# Pixie.net
KiCad netlist of a schematic drawn in EAGLE
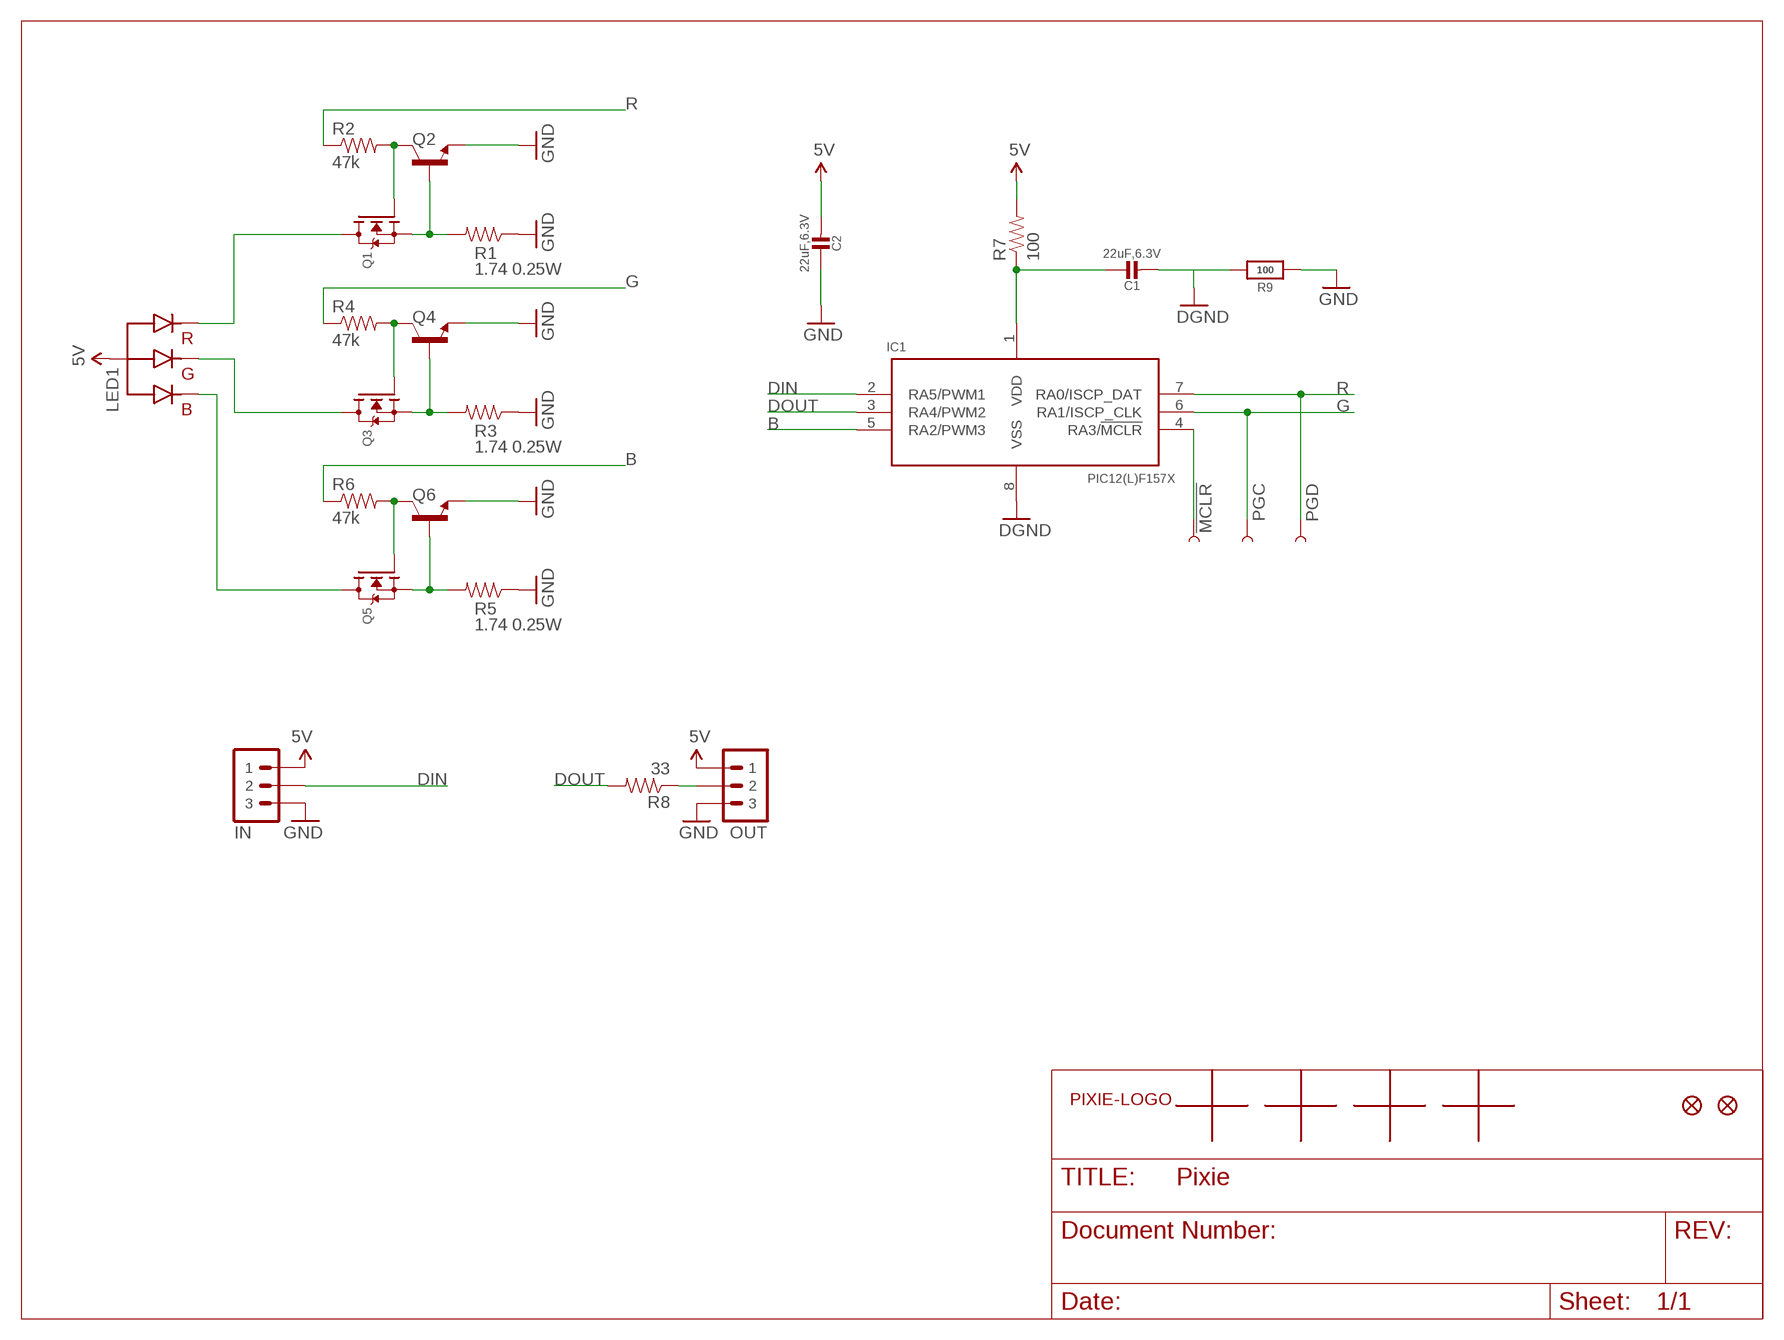
[diagram p0: schematic, sheet 1]

(export (version "E")
  (design (tool "Eeschema 10.0.6"))
  (components
    (comp (ref "!MCLR")
      (value "TEST-POINT3X4")
      (footprint "eagle-import:PAD.03X.04")
      (libsource (lib "eagle-import") (part "TEST-POINT3X4"))
    )
    (comp (ref "C1")
      (value "22uF,6.3V")
      (footprint "eagle-import:_0805MP")
      (libsource (lib "eagle-import") (part "CAP_CERAMIC_0805MP"))
    )
    (comp (ref "C2")
      (value "22uF,6.3V")
      (footprint "eagle-import:_0805MP")
      (libsource (lib "eagle-import") (part "CAP_CERAMIC_0805MP"))
    )
    (comp (ref "IC1")
      (value "PIC12(L)F157X")
      (footprint "eagle-import:MSOP-8")
      (libsource (lib "eagle-import") (part "PIC12(L)F157X"))
    )
    (comp (ref "IN")
      (value "M030.1PWR+SIG")
      (footprint "eagle-import:1X03-0.1PWR+SIG")
      (libsource (lib "eagle-import") (part "M030.1PWR+SIG"))
    )
    (comp (ref "LED1")
      (value "RGBLED_CA")
      (footprint "eagle-import:RGBLED3W4PIN")
      (libsource (lib "eagle-import") (part "RGBLED_CA"))
    )
    (comp (ref "OUT")
      (value "M030.1PWR+SIG")
      (footprint "eagle-import:1X03-0.1PWR+SIG")
      (libsource (lib "eagle-import") (part "M030.1PWR+SIG"))
    )
    (comp (ref "PGC")
      (value "TEST-POINT3X4")
      (footprint "eagle-import:PAD.03X.04")
      (libsource (lib "eagle-import") (part "TEST-POINT3X4"))
    )
    (comp (ref "PGD")
      (value "TEST-POINT3X4")
      (footprint "eagle-import:PAD.03X.04")
      (libsource (lib "eagle-import") (part "TEST-POINT3X4"))
    )
    (comp (ref "Q1")
      (value "IRLML2060TRPBF")
      (footprint "eagle-import:SOT23-3")
      (libsource (lib "eagle-import") (part "IRLML2060TRPBF"))
    )
    (comp (ref "Q2")
      (value "MMBT2222A")
      (footprint "eagle-import:SOT23-3")
      (libsource (lib "eagle-import") (part "MMBT2222A"))
    )
    (comp (ref "Q3")
      (value "IRLML2060TRPBF")
      (footprint "eagle-import:SOT23-3")
      (libsource (lib "eagle-import") (part "IRLML2060TRPBF"))
    )
    (comp (ref "Q4")
      (value "MMBT2222A")
      (footprint "eagle-import:SOT23-3")
      (libsource (lib "eagle-import") (part "MMBT2222A"))
    )
    (comp (ref "Q5")
      (value "IRLML2060TRPBF")
      (footprint "eagle-import:SOT23-3")
      (libsource (lib "eagle-import") (part "IRLML2060TRPBF"))
    )
    (comp (ref "Q6")
      (value "MMBT2222A")
      (footprint "eagle-import:SOT23-3")
      (libsource (lib "eagle-import") (part "MMBT2222A"))
    )
    (comp (ref "R1")
      (value "1.74 0.25W")
      (footprint "eagle-import:1206")
      (libsource (lib "eagle-import") (part "SparkFun-Resistors_RESISTOR1206"))
    )
    (comp (ref "R2")
      (value "47k")
      (footprint "eagle-import:0603-RES")
      (libsource (lib "eagle-import") (part "RESISTOR0603"))
    )
    (comp (ref "R3")
      (value "1.74 0.25W")
      (footprint "eagle-import:1206")
      (libsource (lib "eagle-import") (part "SparkFun-Resistors_RESISTOR1206"))
    )
    (comp (ref "R4")
      (value "47k")
      (footprint "eagle-import:0603-RES")
      (libsource (lib "eagle-import") (part "RESISTOR0603"))
    )
    (comp (ref "R5")
      (value "1.74 0.25W")
      (footprint "eagle-import:1206")
      (libsource (lib "eagle-import") (part "SparkFun-Resistors_RESISTOR1206"))
    )
    (comp (ref "R6")
      (value "47k")
      (footprint "eagle-import:0603-RES")
      (libsource (lib "eagle-import") (part "RESISTOR0603"))
    )
    (comp (ref "R7")
      (value "100")
      (footprint "eagle-import:0603-RES")
      (libsource (lib "eagle-import") (part "RESISTOR0603"))
    )
    (comp (ref "R8")
      (value "33")
      (footprint "eagle-import:0603-RES")
      (libsource (lib "eagle-import") (part "RESISTOR0603"))
    )
    (comp (ref "R9")
      (value "100")
      (footprint "eagle-import:_0603MP")
      (libsource (lib "eagle-import") (part "RESISTOR_0603MP"))
    )
    (comp (ref "U$1")
      (value "ALIGN_CROSS")
      (footprint "eagle-import:ALIGN_CROSS")
      (libsource (lib "eagle-import") (part "ALIGN_CROSS"))
    )
    (comp (ref "U$2")
      (value "ALIGN_CROSS")
      (footprint "eagle-import:ALIGN_CROSS")
      (libsource (lib "eagle-import") (part "ALIGN_CROSS"))
    )
    (comp (ref "U$3")
      (value "ALIGN_CROSS")
      (footprint "eagle-import:ALIGN_CROSS")
      (libsource (lib "eagle-import") (part "ALIGN_CROSS"))
    )
    (comp (ref "U$4")
      (value "ALIGN_CROSS")
      (footprint "eagle-import:ALIGN_CROSS")
      (libsource (lib "eagle-import") (part "ALIGN_CROSS"))
    )
    (comp (ref "U$5")
      (value "PIXIE-LOGO")
      (footprint "eagle-import:PIXIE-LOGO")
      (libsource (lib "eagle-import") (part "PIXIE-LOGO"))
    )
    (comp (ref "U$6")
      (value "FIDUCIAL\"\"")
      (footprint "eagle-import:FIDUCIAL_1MM")
      (libsource (lib "eagle-import") (part "FIDUCIAL{dblquote}{dblquote}"))
    )
    (comp (ref "U$7")
      (value "FIDUCIAL\"\"")
      (footprint "eagle-import:FIDUCIAL_1MM")
      (libsource (lib "eagle-import") (part "FIDUCIAL{dblquote}{dblquote}"))
    )
  )
  (nets
    (net (code "1") (name "/B") (class "Default")
      (node (ref "IC1") (pin "5") (pinfunction "RA2/PWM3_5") (pintype "bidirectional"))
      (node (ref "R6") (pin "1") (pinfunction "1_1") (pintype "passive"))
    )
    (net (code "2") (name "/DIN") (class "Default")
      (node (ref "IC1") (pin "2") (pinfunction "RA5/PWM1_2") (pintype "bidirectional"))
      (node (ref "IN") (pin "P$2") (pinfunction "2_P$2") (pintype "passive"))
    )
    (net (code "3") (name "/DOUT") (class "Default")
      (node (ref "IC1") (pin "3") (pinfunction "RA4/PWM2_3") (pintype "bidirectional"))
      (node (ref "R8") (pin "2") (pinfunction "2_2") (pintype "passive"))
    )
    (net (code "4") (name "/G") (class "Default")
      (node (ref "IC1") (pin "6") (pinfunction "RA1/ISCP_CLK_6") (pintype "bidirectional"))
      (node (ref "PGC") (pin "P$1") (pinfunction "1_P$1") (pintype "bidirectional"))
      (node (ref "R4") (pin "1") (pinfunction "1_1") (pintype "passive"))
    )
    (net (code "5") (name "/R") (class "Default")
      (node (ref "IC1") (pin "7") (pinfunction "RA0/ISCP_DAT_7") (pintype "bidirectional"))
      (node (ref "PGD") (pin "P$1") (pinfunction "1_P$1") (pintype "bidirectional"))
      (node (ref "R2") (pin "1") (pinfunction "1_1") (pintype "passive"))
    )
    (net (code "6") (name "5V") (class "Default")
      (node (ref "C2") (pin "2") (pinfunction "2_2") (pintype "passive"))
      (node (ref "IN") (pin "P$1") (pinfunction "1_P$1") (pintype "passive"))
      (node (ref "LED1") (pin "ANODE") (pinfunction "VCC_ANODE") (pintype "bidirectional"))
      (node (ref "OUT") (pin "P$1") (pinfunction "1_P$1") (pintype "passive"))
      (node (ref "R7") (pin "2") (pinfunction "2_2") (pintype "passive"))
    )
    (net (code "7") (name "DGND") (class "Default")
      (node (ref "C1") (pin "2") (pinfunction "2_2") (pintype "passive"))
      (node (ref "IC1") (pin "8") (pinfunction "VSS_8") (pintype "power_in"))
      (node (ref "R9") (pin "2") (pinfunction "2_2") (pintype "passive"))
    )
    (net (code "8") (name "GND") (class "Default")
      (node (ref "C2") (pin "1") (pinfunction "1_1") (pintype "passive"))
      (node (ref "IN") (pin "P$3") (pinfunction "3_P$3") (pintype "passive"))
      (node (ref "OUT") (pin "P$3") (pinfunction "3_P$3") (pintype "passive"))
      (node (ref "Q2") (pin "2") (pinfunction "E_2") (pintype "passive"))
      (node (ref "Q4") (pin "2") (pinfunction "E_2") (pintype "passive"))
      (node (ref "Q6") (pin "2") (pinfunction "E_2") (pintype "passive"))
      (node (ref "R1") (pin "1") (pinfunction "1_1") (pintype "passive"))
      (node (ref "R3") (pin "1") (pinfunction "1_1") (pintype "passive"))
      (node (ref "R5") (pin "1") (pinfunction "1_1") (pintype "passive"))
      (node (ref "R9") (pin "1") (pinfunction "1_1") (pintype "passive"))
    )
    (net (code "9") (name "Net-(!MCLR-1)") (class "Default")
      (node (ref "!MCLR") (pin "P$1") (pinfunction "1_P$1") (pintype "bidirectional"))
      (node (ref "IC1") (pin "4") (pinfunction "RA3/~{MCLR}_4") (pintype "bidirectional"))
    )
    (net (code "10") (name "Net-(IC1-VDD)") (class "Default")
      (node (ref "C1") (pin "1") (pinfunction "1_1") (pintype "passive"))
      (node (ref "IC1") (pin "1") (pinfunction "VDD_1") (pintype "power_in"))
      (node (ref "R7") (pin "1") (pinfunction "1_1") (pintype "passive"))
    )
    (net (code "11") (name "Net-(LED1-BLUE)") (class "Default")
      (node (ref "LED1") (pin "B") (pinfunction "BLUE_B") (pintype "bidirectional"))
      (node (ref "Q5") (pin "3") (pinfunction "D_3") (pintype "bidirectional"))
    )
    (net (code "12") (name "Net-(LED1-GREEN)") (class "Default")
      (node (ref "LED1") (pin "G") (pinfunction "GREEN_G") (pintype "bidirectional"))
      (node (ref "Q3") (pin "3") (pinfunction "D_3") (pintype "bidirectional"))
    )
    (net (code "13") (name "Net-(LED1-RED)") (class "Default")
      (node (ref "LED1") (pin "R") (pinfunction "RED_R") (pintype "bidirectional"))
      (node (ref "Q1") (pin "3") (pinfunction "D_3") (pintype "bidirectional"))
    )
    (net (code "14") (name "Net-(OUT-2)") (class "Default")
      (node (ref "OUT") (pin "P$2") (pinfunction "2_P$2") (pintype "passive"))
      (node (ref "R8") (pin "1") (pinfunction "1_1") (pintype "passive"))
    )
    (net (code "15") (name "Net-(Q1-G)") (class "Default")
      (node (ref "Q1") (pin "1") (pinfunction "G_1") (pintype "bidirectional"))
      (node (ref "Q2") (pin "3") (pinfunction "C_3") (pintype "passive"))
      (node (ref "R2") (pin "2") (pinfunction "2_2") (pintype "passive"))
    )
    (net (code "16") (name "Net-(Q1-S)") (class "Default")
      (node (ref "Q1") (pin "2") (pinfunction "S_2") (pintype "bidirectional"))
      (node (ref "Q2") (pin "1") (pinfunction "B_1") (pintype "passive"))
      (node (ref "R1") (pin "2") (pinfunction "2_2") (pintype "passive"))
    )
    (net (code "17") (name "Net-(Q3-G)") (class "Default")
      (node (ref "Q3") (pin "1") (pinfunction "G_1") (pintype "bidirectional"))
      (node (ref "Q4") (pin "3") (pinfunction "C_3") (pintype "passive"))
      (node (ref "R4") (pin "2") (pinfunction "2_2") (pintype "passive"))
    )
    (net (code "18") (name "Net-(Q3-S)") (class "Default")
      (node (ref "Q3") (pin "2") (pinfunction "S_2") (pintype "bidirectional"))
      (node (ref "Q4") (pin "1") (pinfunction "B_1") (pintype "passive"))
      (node (ref "R3") (pin "2") (pinfunction "2_2") (pintype "passive"))
    )
    (net (code "19") (name "Net-(Q5-G)") (class "Default")
      (node (ref "Q5") (pin "1") (pinfunction "G_1") (pintype "bidirectional"))
      (node (ref "Q6") (pin "3") (pinfunction "C_3") (pintype "passive"))
      (node (ref "R6") (pin "2") (pinfunction "2_2") (pintype "passive"))
    )
    (net (code "20") (name "Net-(Q5-S)") (class "Default")
      (node (ref "Q5") (pin "2") (pinfunction "S_2") (pintype "bidirectional"))
      (node (ref "Q6") (pin "1") (pinfunction "B_1") (pintype "passive"))
      (node (ref "R5") (pin "2") (pinfunction "2_2") (pintype "passive"))
    )
  )
)
